# bletka_5.net
KiCad netlist of a schematic drawn in EAGLE
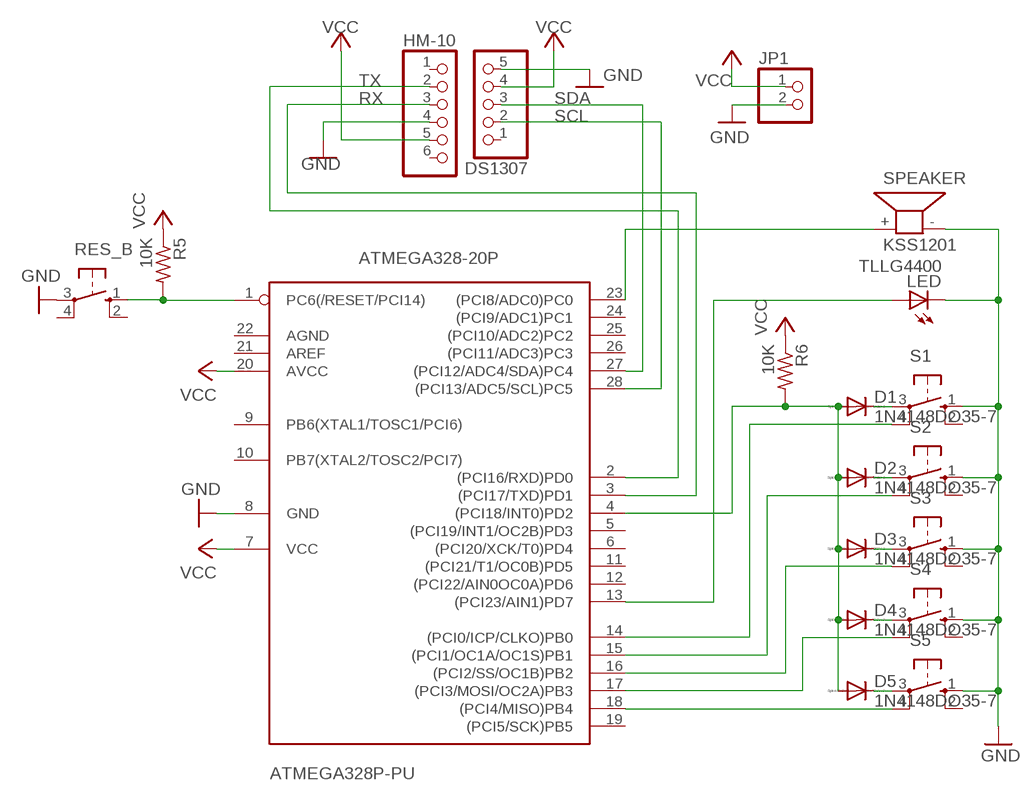
[diagram p0: schematic, sheet 1]

(export (version "E")
  (design (tool "Eeschema 10.0.6"))
  (components
    (comp (ref "ATMEGA328P-PU")
      (value "ATMEGA328-20P")
      (footprint "eagle-import:DIL28-3")
      (libsource (lib "eagle-import") (part "ATMEGA328P-20"))
    )
    (comp (ref "D1")
      (value "1N4148DO35-7")
      (footprint "eagle-import:DO35-7")
      (libsource (lib "eagle-import") (part "1N4148DO35-7"))
    )
    (comp (ref "D2")
      (value "1N4148DO35-7")
      (footprint "eagle-import:DO35-7")
      (libsource (lib "eagle-import") (part "1N4148DO35-7"))
    )
    (comp (ref "D3")
      (value "1N4148DO35-7")
      (footprint "eagle-import:DO35-7")
      (libsource (lib "eagle-import") (part "1N4148DO35-7"))
    )
    (comp (ref "D4")
      (value "1N4148DO35-7")
      (footprint "eagle-import:DO35-7")
      (libsource (lib "eagle-import") (part "1N4148DO35-7"))
    )
    (comp (ref "D5")
      (value "1N4148DO35-7")
      (footprint "eagle-import:DO35-7")
      (libsource (lib "eagle-import") (part "1N4148DO35-7"))
    )
    (comp (ref "DS1307")
      (value "PINHD-1X5")
      (footprint "eagle-import:1X05")
      (libsource (lib "eagle-import") (part "PINHD-1X5"))
    )
    (comp (ref "HM-10")
      (value "PINHD-1X6")
      (footprint "eagle-import:1X06")
      (libsource (lib "eagle-import") (part "PINHD-1X6"))
    )
    (comp (ref "JP1")
      (value "PINHD-1X2")
      (footprint "eagle-import:1X02")
      (libsource (lib "eagle-import") (part "PINHD-1X2"))
    )
    (comp (ref "LED")
      (value "TLLG4400")
      (footprint "eagle-import:LED3MM")
      (fields (field (name "MF") "VISHAY SEMICONDUCTOR"))
      (libsource (lib "eagle-import") (part "TLLG4400"))
    )
    (comp (ref "R5")
      (value "10K")
      (footprint "eagle-import:0207_10")
      (libsource (lib "eagle-import") (part "R-US_0207/10"))
    )
    (comp (ref "R6")
      (value "10K")
      (footprint "eagle-import:0207_10")
      (libsource (lib "eagle-import") (part "R-US_0207/10"))
    )
    (comp (ref "RES_B")
      (value "10-XX")
      (footprint "eagle-import:B3F-10XX")
      (fields (field (name "MPN") "B3F-1000"))
      (libsource (lib "eagle-import") (part "10-XX"))
    )
    (comp (ref "S1")
      (value "10-XX")
      (footprint "eagle-import:B3F-10XX")
      (fields (field (name "MPN") "B3F-1000"))
      (libsource (lib "eagle-import") (part "10-XX"))
    )
    (comp (ref "S2")
      (value "10-XX")
      (footprint "eagle-import:B3F-10XX")
      (fields (field (name "MPN") "B3F-1000"))
      (libsource (lib "eagle-import") (part "10-XX"))
    )
    (comp (ref "S3")
      (value "10-XX")
      (footprint "eagle-import:B3F-10XX")
      (fields (field (name "MPN") "B3F-1000"))
      (libsource (lib "eagle-import") (part "10-XX"))
    )
    (comp (ref "S4")
      (value "10-XX")
      (footprint "eagle-import:B3F-10XX")
      (fields (field (name "MPN") "B3F-1000"))
      (libsource (lib "eagle-import") (part "10-XX"))
    )
    (comp (ref "S5")
      (value "10-XX")
      (footprint "eagle-import:B3F-10XX")
      (fields (field (name "MPN") "B3F-1000"))
      (libsource (lib "eagle-import") (part "10-XX"))
    )
    (comp (ref "SPEAKER")
      (value "KSS1201")
      (footprint "eagle-import:KSS1201")
      (libsource (lib "eagle-import") (part "KSS1201"))
    )
  )
  (nets
    (net (code "1") (name "/RX") (class "Default")
      (node (ref "ATMEGA328P-PU") (pin "3") (pinfunction "(PCI17/TXD)PD1_3") (pintype "bidirectional"))
      (node (ref "HM-10") (pin "3") (pinfunction "3_3") (pintype "passive"))
    )
    (net (code "2") (name "/SCL") (class "Default")
      (node (ref "ATMEGA328P-PU") (pin "28") (pinfunction "(PCI13/ADC5/SCL)PC5_28") (pintype "bidirectional"))
      (node (ref "DS1307") (pin "2") (pinfunction "2_2") (pintype "passive"))
    )
    (net (code "3") (name "/SDA") (class "Default")
      (node (ref "ATMEGA328P-PU") (pin "27") (pinfunction "(PCI12/ADC4/SDA)PC4_27") (pintype "bidirectional"))
      (node (ref "DS1307") (pin "3") (pinfunction "3_3") (pintype "passive"))
    )
    (net (code "4") (name "/TX") (class "Default")
      (node (ref "ATMEGA328P-PU") (pin "2") (pinfunction "(PCI16/RXD)PD0_2") (pintype "bidirectional"))
      (node (ref "HM-10") (pin "2") (pinfunction "2_2") (pintype "passive"))
    )
    (net (code "5") (name "GND") (class "Default")
      (node (ref "ATMEGA328P-PU") (pin "8") (pinfunction "GND_8") (pintype "bidirectional"))
      (node (ref "DS1307") (pin "5") (pinfunction "5_5") (pintype "passive"))
      (node (ref "HM-10") (pin "4") (pinfunction "4_4") (pintype "passive"))
      (node (ref "JP1") (pin "2") (pinfunction "2_2") (pintype "passive"))
      (node (ref "LED") (pin "K") (pinfunction "C_K") (pintype "passive"))
      (node (ref "RES_B") (pin "3") (pinfunction "P_3") (pintype "passive"))
      (node (ref "S1") (pin "1") (pinfunction "S_1") (pintype "passive"))
      (node (ref "S2") (pin "1") (pinfunction "S_1") (pintype "passive"))
      (node (ref "S3") (pin "1") (pinfunction "S_1") (pintype "passive"))
      (node (ref "S4") (pin "1") (pinfunction "S_1") (pintype "passive"))
      (node (ref "S5") (pin "1") (pinfunction "S_1") (pintype "passive"))
      (node (ref "SPEAKER") (pin "-") (pinfunction "2_-") (pintype "passive"))
    )
    (net (code "6") (name "Net-(ATMEGA328P-PU-(PCI0{slash}ICP{slash}CLKO)PB0)") (class "Default")
      (node (ref "ATMEGA328P-PU") (pin "14") (pinfunction "(PCI0/ICP/CLKO)PB0_14") (pintype "bidirectional"))
      (node (ref "S1") (pin "4") (pinfunction "P1_4") (pintype "passive"))
    )
    (net (code "7") (name "Net-(ATMEGA328P-PU-(PCI1{slash}OC1A{slash}OC1S)PB1)") (class "Default")
      (node (ref "ATMEGA328P-PU") (pin "15") (pinfunction "(PCI1/OC1A/OC1S)PB1_15") (pintype "bidirectional"))
      (node (ref "S2") (pin "4") (pinfunction "P1_4") (pintype "passive"))
    )
    (net (code "8") (name "Net-(ATMEGA328P-PU-(PCI2{slash}SS{slash}OC1B)PB2)") (class "Default")
      (node (ref "ATMEGA328P-PU") (pin "16") (pinfunction "(PCI2/SS/OC1B)PB2_16") (pintype "bidirectional"))
      (node (ref "S3") (pin "4") (pinfunction "P1_4") (pintype "passive"))
    )
    (net (code "9") (name "Net-(ATMEGA328P-PU-(PCI3{slash}MOSI{slash}OC2A)PB3)") (class "Default")
      (node (ref "ATMEGA328P-PU") (pin "17") (pinfunction "(PCI3/MOSI/OC2A)PB3_17") (pintype "bidirectional"))
      (node (ref "S4") (pin "4") (pinfunction "P1_4") (pintype "passive"))
    )
    (net (code "10") (name "Net-(ATMEGA328P-PU-(PCI4{slash}MISO)PB4)") (class "Default")
      (node (ref "ATMEGA328P-PU") (pin "18") (pinfunction "(PCI4/MISO)PB4_18") (pintype "bidirectional"))
      (node (ref "S5") (pin "4") (pinfunction "P1_4") (pintype "passive"))
    )
    (net (code "11") (name "Net-(ATMEGA328P-PU-(PCI8{slash}ADC0)PC0)") (class "Default")
      (node (ref "ATMEGA328P-PU") (pin "23") (pinfunction "(PCI8/ADC0)PC0_23") (pintype "bidirectional"))
      (node (ref "SPEAKER") (pin "+") (pinfunction "1_+") (pintype "passive"))
    )
    (net (code "12") (name "Net-(ATMEGA328P-PU-(PCI18{slash}INT0)PD2)") (class "Default")
      (node (ref "ATMEGA328P-PU") (pin "4") (pinfunction "(PCI18/INT0)PD2_4") (pintype "bidirectional"))
      (node (ref "D1") (pin "A") (pinfunction "A_A") (pintype "passive"))
      (node (ref "D2") (pin "A") (pinfunction "A_A") (pintype "passive"))
      (node (ref "D3") (pin "A") (pinfunction "A_A") (pintype "passive"))
      (node (ref "D4") (pin "A") (pinfunction "A_A") (pintype "passive"))
      (node (ref "D5") (pin "A") (pinfunction "A_A") (pintype "passive"))
      (node (ref "R6") (pin "2") (pinfunction "2_2") (pintype "passive"))
    )
    (net (code "13") (name "Net-(ATMEGA328P-PU-(PCI23{slash}AIN1)PD7)") (class "Default")
      (node (ref "ATMEGA328P-PU") (pin "13") (pinfunction "(PCI23/AIN1)PD7_13") (pintype "bidirectional"))
      (node (ref "LED") (pin "A") (pinfunction "A_A") (pintype "passive"))
    )
    (net (code "14") (name "Net-(ATMEGA328P-PU-PC6({slash}RESET{slash}PCI14))") (class "Default")
      (node (ref "ATMEGA328P-PU") (pin "1") (pinfunction "PC6(/RESET/PCI14)_1") (pintype "bidirectional"))
      (node (ref "R5") (pin "2") (pinfunction "2_2") (pintype "passive"))
      (node (ref "RES_B") (pin "1") (pinfunction "S_1") (pintype "passive"))
    )
    (net (code "15") (name "Net-(S1-P)") (class "Default")
      (node (ref "D1") (pin "C") (pinfunction "C_C") (pintype "passive"))
      (node (ref "S1") (pin "3") (pinfunction "P_3") (pintype "passive"))
    )
    (net (code "16") (name "Net-(S2-P)") (class "Default")
      (node (ref "D2") (pin "C") (pinfunction "C_C") (pintype "passive"))
      (node (ref "S2") (pin "3") (pinfunction "P_3") (pintype "passive"))
    )
    (net (code "17") (name "Net-(S3-P)") (class "Default")
      (node (ref "D3") (pin "C") (pinfunction "C_C") (pintype "passive"))
      (node (ref "S3") (pin "3") (pinfunction "P_3") (pintype "passive"))
    )
    (net (code "18") (name "Net-(S4-P)") (class "Default")
      (node (ref "D4") (pin "C") (pinfunction "C_C") (pintype "passive"))
      (node (ref "S4") (pin "3") (pinfunction "P_3") (pintype "passive"))
    )
    (net (code "19") (name "Net-(S5-P)") (class "Default")
      (node (ref "D5") (pin "C") (pinfunction "C_C") (pintype "passive"))
      (node (ref "S5") (pin "3") (pinfunction "P_3") (pintype "passive"))
    )
    (net (code "20") (name "VCC") (class "Default")
      (node (ref "ATMEGA328P-PU") (pin "20") (pinfunction "AVCC_20") (pintype "bidirectional"))
      (node (ref "ATMEGA328P-PU") (pin "7") (pinfunction "VCC_7") (pintype "bidirectional"))
      (node (ref "DS1307") (pin "4") (pinfunction "4_4") (pintype "passive"))
      (node (ref "HM-10") (pin "5") (pinfunction "5_5") (pintype "passive"))
      (node (ref "JP1") (pin "1") (pinfunction "1_1") (pintype "passive"))
      (node (ref "R5") (pin "1") (pinfunction "1_1") (pintype "passive"))
      (node (ref "R6") (pin "1") (pinfunction "1_1") (pintype "passive"))
    )
    (net (code "21") (name "unconnected-(ATMEGA328P-PU-(PCI5{slash}SCK)PB5-Pad19)") (class "Default")
      (node (ref "ATMEGA328P-PU") (pin "19") (pinfunction "(PCI5/SCK)PB5_19") (pintype "bidirectional"))
    )
    (net (code "22") (name "unconnected-(ATMEGA328P-PU-(PCI9{slash}ADC1)PC1-Pad24)") (class "Default")
      (node (ref "ATMEGA328P-PU") (pin "24") (pinfunction "(PCI9/ADC1)PC1_24") (pintype "bidirectional"))
    )
    (net (code "23") (name "unconnected-(ATMEGA328P-PU-(PCI10{slash}ADC2)PC2-Pad25)") (class "Default")
      (node (ref "ATMEGA328P-PU") (pin "25") (pinfunction "(PCI10/ADC2)PC2_25") (pintype "bidirectional"))
    )
    (net (code "24") (name "unconnected-(ATMEGA328P-PU-(PCI11{slash}ADC3)PC3-Pad26)") (class "Default")
      (node (ref "ATMEGA328P-PU") (pin "26") (pinfunction "(PCI11/ADC3)PC3_26") (pintype "bidirectional"))
    )
    (net (code "25") (name "unconnected-(ATMEGA328P-PU-(PCI19{slash}INT1{slash}OC2B)PD3-Pad5)") (class "Default")
      (node (ref "ATMEGA328P-PU") (pin "5") (pinfunction "(PCI19/INT1/OC2B)PD3_5") (pintype "bidirectional"))
    )
    (net (code "26") (name "unconnected-(ATMEGA328P-PU-(PCI20{slash}XCK{slash}T0)PD4-Pad6)") (class "Default")
      (node (ref "ATMEGA328P-PU") (pin "6") (pinfunction "(PCI20/XCK/T0)PD4_6") (pintype "bidirectional"))
    )
    (net (code "27") (name "unconnected-(ATMEGA328P-PU-(PCI21{slash}T1{slash}OC0B)PD5-Pad11)") (class "Default")
      (node (ref "ATMEGA328P-PU") (pin "11") (pinfunction "(PCI21/T1/OC0B)PD5_11") (pintype "bidirectional"))
    )
    (net (code "28") (name "unconnected-(ATMEGA328P-PU-(PCI22{slash}AIN0OC0A)PD6-Pad12)") (class "Default")
      (node (ref "ATMEGA328P-PU") (pin "12") (pinfunction "(PCI22/AIN0OC0A)PD6_12") (pintype "bidirectional"))
    )
    (net (code "29") (name "unconnected-(ATMEGA328P-PU-AGND-Pad22)") (class "Default")
      (node (ref "ATMEGA328P-PU") (pin "22") (pinfunction "AGND_22") (pintype "bidirectional"))
    )
    (net (code "30") (name "unconnected-(ATMEGA328P-PU-AREF-Pad21)") (class "Default")
      (node (ref "ATMEGA328P-PU") (pin "21") (pinfunction "AREF_21") (pintype "bidirectional"))
    )
    (net (code "31") (name "unconnected-(ATMEGA328P-PU-PB6(XTAL1{slash}TOSC1{slash}PCI6)-Pad9)") (class "Default")
      (node (ref "ATMEGA328P-PU") (pin "9") (pinfunction "PB6(XTAL1/TOSC1/PCI6)_9") (pintype "bidirectional"))
    )
    (net (code "32") (name "unconnected-(ATMEGA328P-PU-PB7(XTAL2{slash}TOSC2{slash}PCI7)-Pad10)") (class "Default")
      (node (ref "ATMEGA328P-PU") (pin "10") (pinfunction "PB7(XTAL2/TOSC2/PCI7)_10") (pintype "bidirectional"))
    )
    (net (code "33") (name "unconnected-(DS1307-Pad1)") (class "Default")
      (node (ref "DS1307") (pin "1") (pinfunction "1_1") (pintype "passive"))
    )
    (net (code "34") (name "unconnected-(HM-10-Pad1)") (class "Default")
      (node (ref "HM-10") (pin "1") (pinfunction "1_1") (pintype "passive"))
    )
    (net (code "35") (name "unconnected-(HM-10-Pad6)") (class "Default")
      (node (ref "HM-10") (pin "6") (pinfunction "6_6") (pintype "passive"))
    )
    (net (code "36") (name "unconnected-(RES_B-P1-Pad4)") (class "Default")
      (node (ref "RES_B") (pin "4") (pinfunction "P1_4") (pintype "passive"))
    )
    (net (code "37") (name "unconnected-(RES_B-S1-Pad2)") (class "Default")
      (node (ref "RES_B") (pin "2") (pinfunction "S1_2") (pintype "passive"))
    )
    (net (code "38") (name "unconnected-(S1-S1-Pad2)") (class "Default")
      (node (ref "S1") (pin "2") (pinfunction "S1_2") (pintype "passive"))
    )
    (net (code "39") (name "unconnected-(S2-S1-Pad2)") (class "Default")
      (node (ref "S2") (pin "2") (pinfunction "S1_2") (pintype "passive"))
    )
    (net (code "40") (name "unconnected-(S3-S1-Pad2)") (class "Default")
      (node (ref "S3") (pin "2") (pinfunction "S1_2") (pintype "passive"))
    )
    (net (code "41") (name "unconnected-(S4-S1-Pad2)") (class "Default")
      (node (ref "S4") (pin "2") (pinfunction "S1_2") (pintype "passive"))
    )
    (net (code "42") (name "unconnected-(S5-S1-Pad2)") (class "Default")
      (node (ref "S5") (pin "2") (pinfunction "S1_2") (pintype "passive"))
    )
  )
)
